# ccnor_stm32_v25-sync-unified-ss.net
KiCad netlist of a schematic drawn in EAGLE
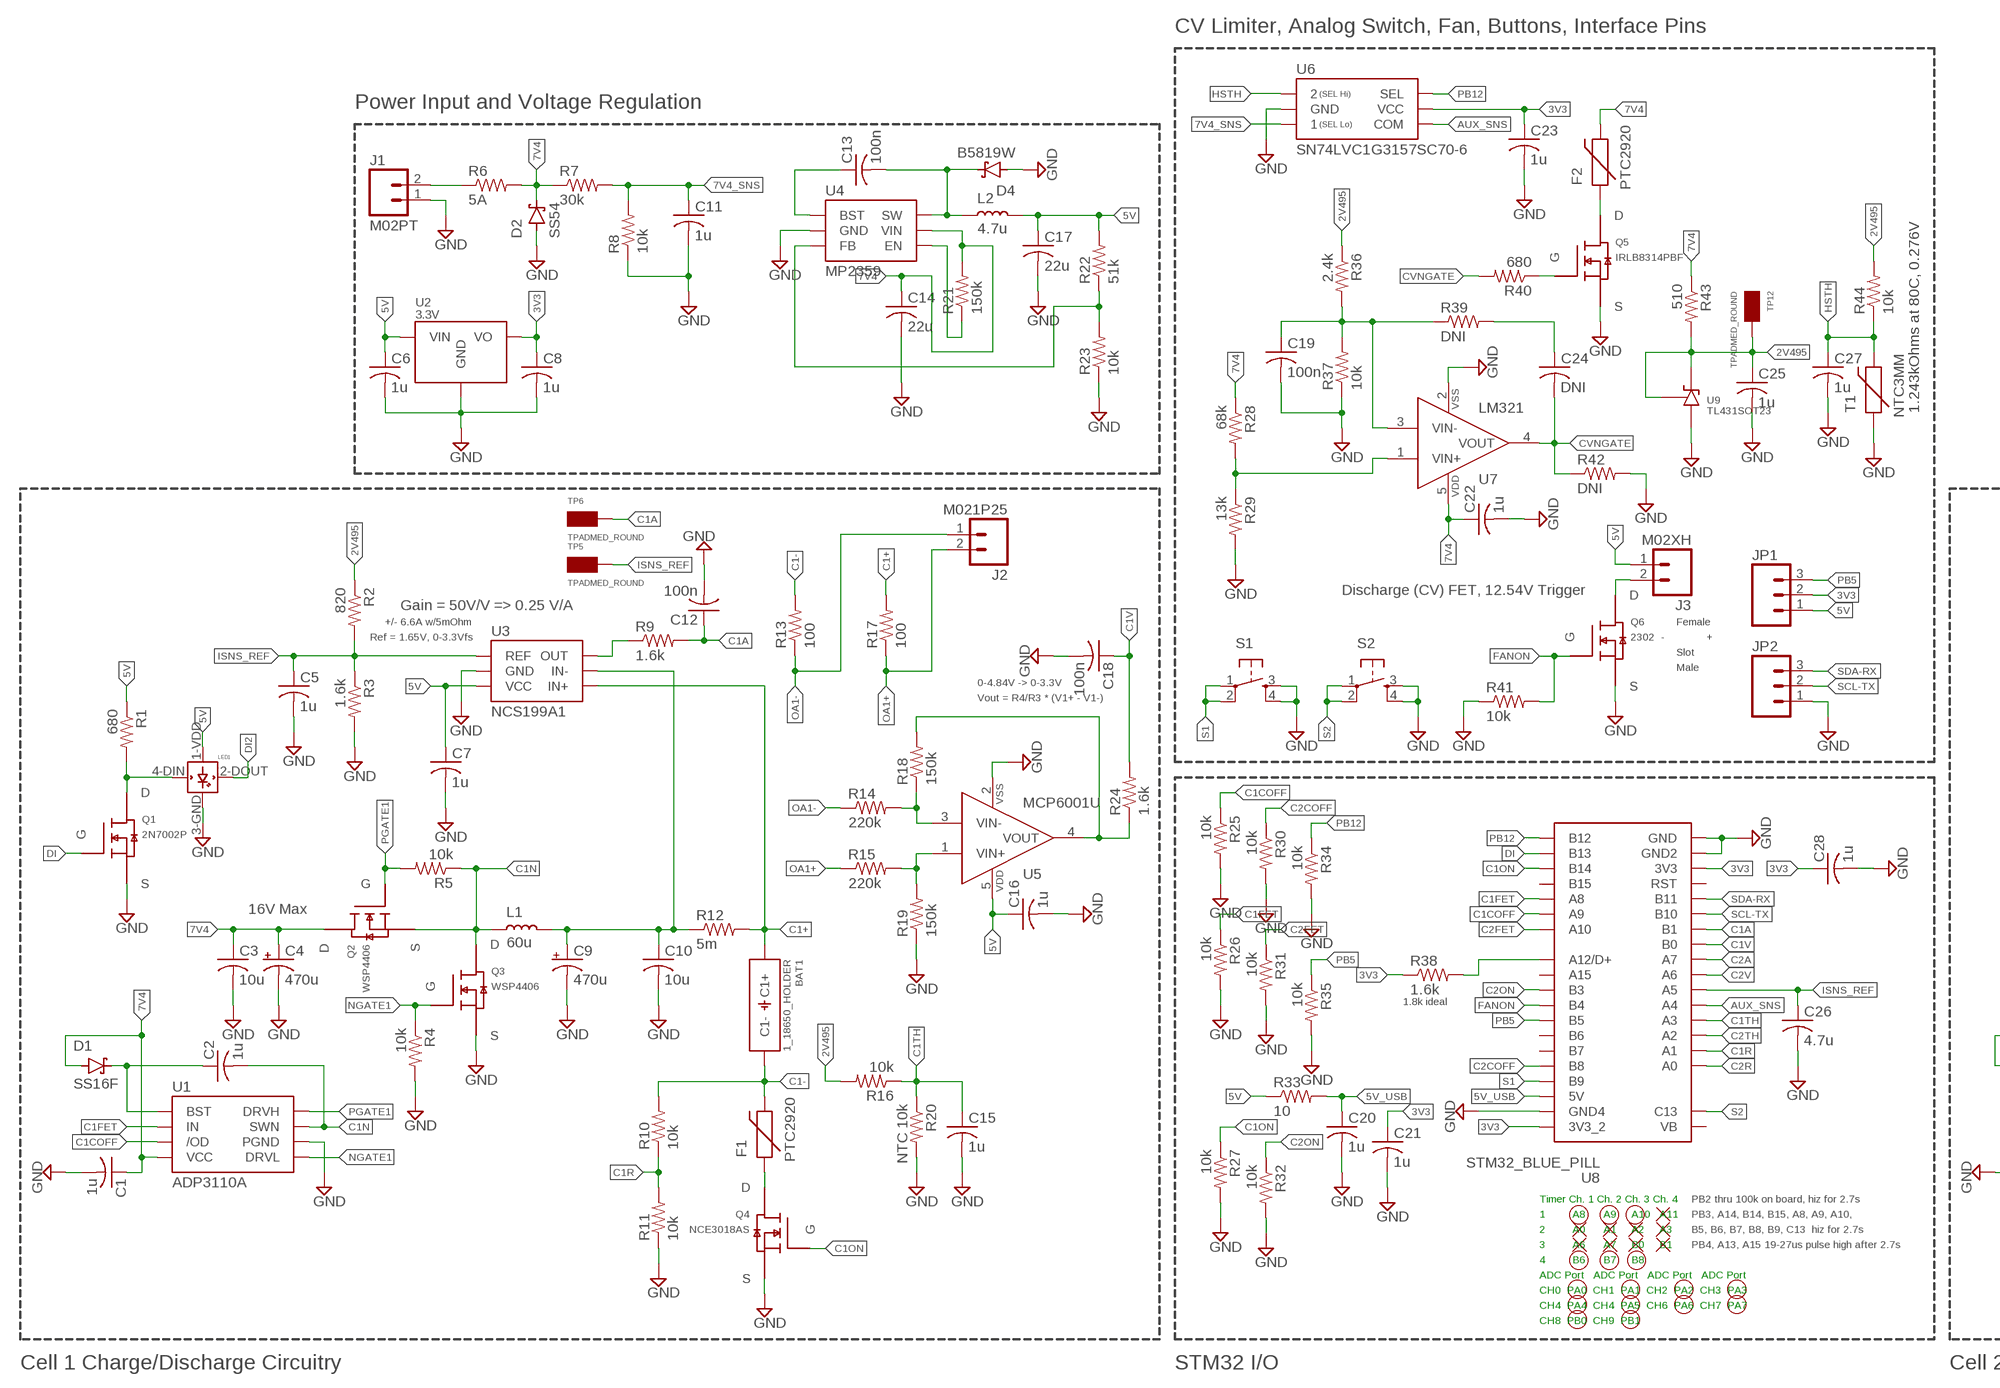
[diagram p0: schematic, sheet 1, part 1 of 2]
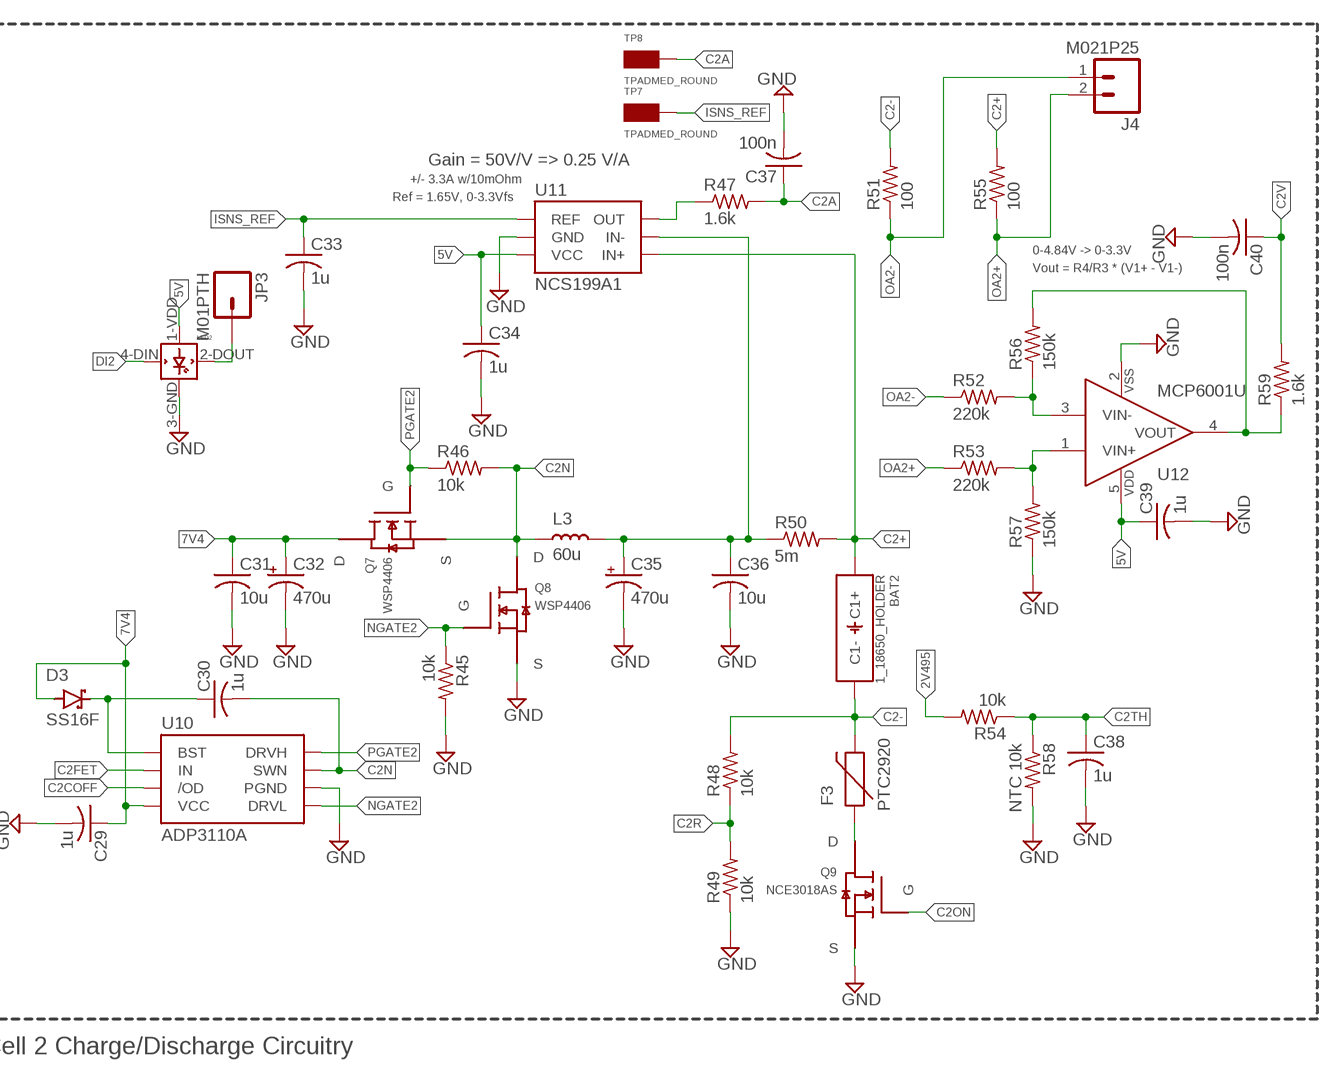
[diagram p1: schematic, sheet 1, part 2 of 2]

(export (version "E")
  (design (tool "Eeschema 10.0.6"))
  (components
    (comp (ref "BAT1")
      (value "1_18650_HOLDER")
      (footprint "eagle-import:1S_18650_SMD_NH")
      (libsource (lib "eagle-import") (part "1_18650_HOLDER"))
    )
    (comp (ref "BAT2")
      (value "1_18650_HOLDER")
      (footprint "eagle-import:1S_18650_SMD_NH")
      (libsource (lib "eagle-import") (part "1_18650_HOLDER"))
    )
    (comp (ref "C1")
      (value "1u")
      (footprint "eagle-import:C0402")
      (libsource (lib "eagle-import") (part "C-USC0402"))
    )
    (comp (ref "C2")
      (value "1u")
      (footprint "eagle-import:C0603")
      (libsource (lib "eagle-import") (part "C-USC0603"))
    )
    (comp (ref "C3")
      (value "10u")
      (footprint "eagle-import:C1206")
      (libsource (lib "eagle-import") (part "C-USC1206"))
    )
    (comp (ref "C4")
      (value "470u")
      (footprint "eagle-import:E2,5-7")
      (libsource (lib "eagle-import") (part "CPOL-USE2.5-7"))
    )
    (comp (ref "C5")
      (value "1u")
      (footprint "eagle-import:C0402")
      (libsource (lib "eagle-import") (part "C-USC0402"))
    )
    (comp (ref "C6")
      (value "1u")
      (footprint "eagle-import:C0402")
      (libsource (lib "eagle-import") (part "C-USC0402"))
    )
    (comp (ref "C7")
      (value "1u")
      (footprint "eagle-import:C0402")
      (libsource (lib "eagle-import") (part "C-USC0402"))
    )
    (comp (ref "C8")
      (value "1u")
      (footprint "eagle-import:C0402")
      (libsource (lib "eagle-import") (part "C-USC0402"))
    )
    (comp (ref "C9")
      (value "470u")
      (footprint "eagle-import:E2,5-7")
      (libsource (lib "eagle-import") (part "CPOL-USE2.5-7"))
    )
    (comp (ref "C10")
      (value "10u")
      (footprint "eagle-import:C1206")
      (libsource (lib "eagle-import") (part "C-USC1206"))
    )
    (comp (ref "C11")
      (value "1u")
      (footprint "eagle-import:C0402")
      (libsource (lib "eagle-import") (part "C-USC0402"))
    )
    (comp (ref "C12")
      (value "100n")
      (footprint "eagle-import:C0402")
      (libsource (lib "eagle-import") (part "C-USC0402"))
    )
    (comp (ref "C13")
      (value "100n")
      (footprint "eagle-import:C0402")
      (libsource (lib "eagle-import") (part "C-USC0402"))
    )
    (comp (ref "C14")
      (value "22u")
      (footprint "eagle-import:C0805")
      (libsource (lib "eagle-import") (part "C-USC0805"))
    )
    (comp (ref "C15")
      (value "1u")
      (footprint "eagle-import:C0402")
      (libsource (lib "eagle-import") (part "C-USC0402"))
    )
    (comp (ref "C16")
      (value "1u")
      (footprint "eagle-import:C0402")
      (libsource (lib "eagle-import") (part "C-USC0402"))
    )
    (comp (ref "C17")
      (value "22u")
      (footprint "eagle-import:C0603")
      (libsource (lib "eagle-import") (part "C-USC0603"))
    )
    (comp (ref "C18")
      (value "100n")
      (footprint "eagle-import:C0402")
      (libsource (lib "eagle-import") (part "C-USC0402"))
    )
    (comp (ref "C19")
      (value "100n")
      (footprint "eagle-import:C0402")
      (libsource (lib "eagle-import") (part "C-USC0402"))
    )
    (comp (ref "C20")
      (value "1u")
      (footprint "eagle-import:C0402")
      (libsource (lib "eagle-import") (part "C-USC0402"))
    )
    (comp (ref "C21")
      (value "1u")
      (footprint "eagle-import:C0402")
      (libsource (lib "eagle-import") (part "C-USC0402"))
    )
    (comp (ref "C22")
      (value "1u")
      (footprint "eagle-import:C0402")
      (libsource (lib "eagle-import") (part "C-USC0402"))
    )
    (comp (ref "C23")
      (value "1u")
      (footprint "eagle-import:C0402")
      (libsource (lib "eagle-import") (part "C-USC0402"))
    )
    (comp (ref "C24")
      (value "DNI")
      (footprint "eagle-import:C0402")
      (libsource (lib "eagle-import") (part "C-USC0402"))
    )
    (comp (ref "C25")
      (value "1u")
      (footprint "eagle-import:C0402")
      (libsource (lib "eagle-import") (part "C-USC0402"))
    )
    (comp (ref "C26")
      (value "4.7u")
      (footprint "eagle-import:C0402")
      (libsource (lib "eagle-import") (part "C-USC0402"))
    )
    (comp (ref "C27")
      (value "1u")
      (footprint "eagle-import:C0402")
      (libsource (lib "eagle-import") (part "C-USC0402"))
    )
    (comp (ref "C28")
      (value "1u")
      (footprint "eagle-import:C0402")
      (libsource (lib "eagle-import") (part "C-USC0402"))
    )
    (comp (ref "C29")
      (value "1u")
      (footprint "eagle-import:C0402")
      (libsource (lib "eagle-import") (part "C-USC0402"))
    )
    (comp (ref "C30")
      (value "1u")
      (footprint "eagle-import:C0603")
      (libsource (lib "eagle-import") (part "C-USC0603"))
    )
    (comp (ref "C31")
      (value "10u")
      (footprint "eagle-import:C1206")
      (libsource (lib "eagle-import") (part "C-USC1206"))
    )
    (comp (ref "C32")
      (value "470u")
      (footprint "eagle-import:E2,5-7")
      (libsource (lib "eagle-import") (part "CPOL-USE2.5-7"))
    )
    (comp (ref "C33")
      (value "1u")
      (footprint "eagle-import:C0402")
      (libsource (lib "eagle-import") (part "C-USC0402"))
    )
    (comp (ref "C34")
      (value "1u")
      (footprint "eagle-import:C0402")
      (libsource (lib "eagle-import") (part "C-USC0402"))
    )
    (comp (ref "C35")
      (value "470u")
      (footprint "eagle-import:E2,5-7")
      (libsource (lib "eagle-import") (part "CPOL-USE2.5-7"))
    )
    (comp (ref "C36")
      (value "10u")
      (footprint "eagle-import:C1206")
      (libsource (lib "eagle-import") (part "C-USC1206"))
    )
    (comp (ref "C37")
      (value "100n")
      (footprint "eagle-import:C0402")
      (libsource (lib "eagle-import") (part "C-USC0402"))
    )
    (comp (ref "C38")
      (value "1u")
      (footprint "eagle-import:C0402")
      (libsource (lib "eagle-import") (part "C-USC0402"))
    )
    (comp (ref "C39")
      (value "1u")
      (footprint "eagle-import:C0402")
      (libsource (lib "eagle-import") (part "C-USC0402"))
    )
    (comp (ref "C40")
      (value "100n")
      (footprint "eagle-import:C0402")
      (libsource (lib "eagle-import") (part "C-USC0402"))
    )
    (comp (ref "D1")
      (value "SS16F")
      (footprint "eagle-import:SOD123")
      (libsource (lib "eagle-import") (part "DIODE_SCHOTTKYCDBM140-G"))
    )
    (comp (ref "D2")
      (value "SS54")
      (footprint "eagle-import:SMA")
      (libsource (lib "eagle-import") (part "SS54"))
    )
    (comp (ref "D3")
      (value "SS16F")
      (footprint "eagle-import:SOD123")
      (libsource (lib "eagle-import") (part "DIODE_SCHOTTKYCDBM140-G"))
    )
    (comp (ref "D4")
      (value "B5819W")
      (footprint "eagle-import:SOD123W")
      (libsource (lib "eagle-import") (part "PMEG3020ER"))
    )
    (comp (ref "F1")
      (value "PTC2920")
      (footprint "eagle-import:2920")
      (libsource (lib "eagle-import") (part "PTC2920"))
    )
    (comp (ref "F2")
      (value "PTC2920")
      (footprint "eagle-import:2920")
      (libsource (lib "eagle-import") (part "PTC2920"))
    )
    (comp (ref "F3")
      (value "PTC2920")
      (footprint "eagle-import:2920")
      (libsource (lib "eagle-import") (part "PTC2920"))
    )
    (comp (ref "J1")
      (value "M02PT")
      (footprint "eagle-import:PHOENIXCONTACT1935161")
      (libsource (lib "eagle-import") (part "M02PT"))
    )
    (comp (ref "J2")
      (value "M021P25")
      (footprint "eagle-import:M02_1P25MM")
      (libsource (lib "eagle-import") (part "M021P25"))
    )
    (comp (ref "J3")
      (value "M02XH")
      (footprint "eagle-import:B2B-XH-A")
      (libsource (lib "eagle-import") (part "M02XH"))
    )
    (comp (ref "J4")
      (value "M021P25")
      (footprint "eagle-import:M02_1P25MM")
      (libsource (lib "eagle-import") (part "M021P25"))
    )
    (comp (ref "JP1")
      (value "M03PTH")
      (footprint "eagle-import:1X03")
      (libsource (lib "eagle-import") (part "M03PTH"))
    )
    (comp (ref "JP2")
      (value "M03PTH")
      (footprint "eagle-import:1X03")
      (libsource (lib "eagle-import") (part "M03PTH"))
    )
    (comp (ref "JP3")
      (value "M01PTH")
      (footprint "eagle-import:1X01")
      (libsource (lib "eagle-import") (part "M01PTH"))
    )
    (comp (ref "L1")
      (value "60u")
      (footprint "eagle-import:INDUCTOR_10A_8.2MMX21MM")
      (libsource (lib "eagle-import") (part "INDUCTOR10A"))
    )
    (comp (ref "L2")
      (value "4.7u")
      (footprint "eagle-import:0805")
      (libsource (lib "eagle-import") (part "INDUCTOR0805"))
    )
    (comp (ref "L3")
      (value "60u")
      (footprint "eagle-import:INDUCTOR_10A_8.2MMX21MM")
      (libsource (lib "eagle-import") (part "INDUCTOR10A"))
    )
    (comp (ref "LED1")
      (value "WS2812B")
      (footprint "eagle-import:WS2812B")
      (libsource (lib "eagle-import") (part "WS2812B"))
    )
    (comp (ref "LED2")
      (value "WS2812B")
      (footprint "eagle-import:WS2812B")
      (libsource (lib "eagle-import") (part "WS2812B"))
    )
    (comp (ref "Q1")
      (value "2N7002P")
      (footprint "eagle-import:SOT23")
      (libsource (lib "eagle-import") (part "2N7002P"))
    )
    (comp (ref "Q2")
      (value "WSP4406")
      (footprint "eagle-import:8-SOIC")
      (libsource (lib "eagle-import") (part "N-MOSFET-SOIC8"))
    )
    (comp (ref "Q3")
      (value "WSP4406")
      (footprint "eagle-import:8-SOIC")
      (libsource (lib "eagle-import") (part "N-MOSFET-SOIC8"))
    )
    (comp (ref "Q4")
      (value "NCE3018AS")
      (footprint "eagle-import:8-SOIC")
      (libsource (lib "eagle-import") (part "N-MOSFET-SOIC8"))
    )
    (comp (ref "Q5")
      (value "IRLB8314PBF")
      (footprint "eagle-import:TO-220")
      (libsource (lib "eagle-import") (part "IRLB8314PBF"))
    )
    (comp (ref "Q6")
      (value "2302")
      (footprint "eagle-import:SOT23")
      (libsource (lib "eagle-import") (part "2N7002P"))
    )
    (comp (ref "Q7")
      (value "WSP4406")
      (footprint "eagle-import:8-SOIC")
      (libsource (lib "eagle-import") (part "N-MOSFET-SOIC8"))
    )
    (comp (ref "Q8")
      (value "WSP4406")
      (footprint "eagle-import:8-SOIC")
      (libsource (lib "eagle-import") (part "N-MOSFET-SOIC8"))
    )
    (comp (ref "Q9")
      (value "NCE3018AS")
      (footprint "eagle-import:8-SOIC")
      (libsource (lib "eagle-import") (part "N-MOSFET-SOIC8"))
    )
    (comp (ref "R1")
      (value "680")
      (footprint "eagle-import:R0402")
      (libsource (lib "eagle-import") (part "R-US_R0402"))
    )
    (comp (ref "R2")
      (value "820")
      (footprint "eagle-import:R0402")
      (libsource (lib "eagle-import") (part "R-US_R0402"))
    )
    (comp (ref "R3")
      (value "1.6k")
      (footprint "eagle-import:R0402")
      (libsource (lib "eagle-import") (part "R-US_R0402"))
    )
    (comp (ref "R4")
      (value "10k")
      (footprint "eagle-import:R0402")
      (libsource (lib "eagle-import") (part "R-US_R0402"))
    )
    (comp (ref "R5")
      (value "10k")
      (footprint "eagle-import:R0402")
      (libsource (lib "eagle-import") (part "R-US_R0402"))
    )
    (comp (ref "R6")
      (value "5A")
      (footprint "eagle-import:R1206")
      (libsource (lib "eagle-import") (part "R-US_R1206"))
    )
    (comp (ref "R7")
      (value "30k")
      (footprint "eagle-import:R0402")
      (libsource (lib "eagle-import") (part "R-US_R0402"))
    )
    (comp (ref "R8")
      (value "10k")
      (footprint "eagle-import:R0402")
      (libsource (lib "eagle-import") (part "R-US_R0402"))
    )
    (comp (ref "R9")
      (value "1.6k")
      (footprint "eagle-import:R0402")
      (libsource (lib "eagle-import") (part "R-US_R0402"))
    )
    (comp (ref "R10")
      (value "10k")
      (footprint "eagle-import:R0402")
      (libsource (lib "eagle-import") (part "R-US_R0402"))
    )
    (comp (ref "R11")
      (value "10k")
      (footprint "eagle-import:R0402")
      (libsource (lib "eagle-import") (part "R-US_R0402"))
    )
    (comp (ref "R12")
      (value "5m")
      (footprint "eagle-import:R1206")
      (libsource (lib "eagle-import") (part "R-US_R1206"))
    )
    (comp (ref "R13")
      (value "100")
      (footprint "eagle-import:R0402")
      (libsource (lib "eagle-import") (part "R-US_R0402"))
    )
    (comp (ref "R14")
      (value "220k")
      (footprint "eagle-import:R0402")
      (libsource (lib "eagle-import") (part "R-US_R0402"))
    )
    (comp (ref "R15")
      (value "220k")
      (footprint "eagle-import:R0402")
      (libsource (lib "eagle-import") (part "R-US_R0402"))
    )
    (comp (ref "R16")
      (value "10k")
      (footprint "eagle-import:R0402")
      (libsource (lib "eagle-import") (part "R-US_R0402"))
    )
    (comp (ref "R17")
      (value "100")
      (footprint "eagle-import:R0402")
      (libsource (lib "eagle-import") (part "R-US_R0402"))
    )
    (comp (ref "R18")
      (value "150k")
      (footprint "eagle-import:R0402")
      (libsource (lib "eagle-import") (part "R-US_R0402"))
    )
    (comp (ref "R19")
      (value "150k")
      (footprint "eagle-import:R0402")
      (libsource (lib "eagle-import") (part "R-US_R0402"))
    )
    (comp (ref "R20")
      (value "NTC 10k")
      (footprint "eagle-import:R0402")
      (libsource (lib "eagle-import") (part "R-US_R0402"))
    )
    (comp (ref "R21")
      (value "150k")
      (footprint "eagle-import:R0402")
      (libsource (lib "eagle-import") (part "R-US_R0402"))
    )
    (comp (ref "R22")
      (value "51k")
      (footprint "eagle-import:R0402")
      (libsource (lib "eagle-import") (part "R-US_R0402"))
    )
    (comp (ref "R23")
      (value "10k")
      (footprint "eagle-import:R0402")
      (libsource (lib "eagle-import") (part "R-US_R0402"))
    )
    (comp (ref "R24")
      (value "1.6k")
      (footprint "eagle-import:R0402")
      (libsource (lib "eagle-import") (part "R-US_R0402"))
    )
    (comp (ref "R25")
      (value "10k")
      (footprint "eagle-import:R0402")
      (libsource (lib "eagle-import") (part "R-US_R0402"))
    )
    (comp (ref "R26")
      (value "10k")
      (footprint "eagle-import:R0402")
      (libsource (lib "eagle-import") (part "R-US_R0402"))
    )
    (comp (ref "R27")
      (value "10k")
      (footprint "eagle-import:R0402")
      (libsource (lib "eagle-import") (part "R-US_R0402"))
    )
    (comp (ref "R28")
      (value "68k")
      (footprint "eagle-import:R0402")
      (libsource (lib "eagle-import") (part "R-US_R0402"))
    )
    (comp (ref "R29")
      (value "13k")
      (footprint "eagle-import:R0402")
      (libsource (lib "eagle-import") (part "R-US_R0402"))
    )
    (comp (ref "R30")
      (value "10k")
      (footprint "eagle-import:R0402")
      (libsource (lib "eagle-import") (part "R-US_R0402"))
    )
    (comp (ref "R31")
      (value "10k")
      (footprint "eagle-import:R0402")
      (libsource (lib "eagle-import") (part "R-US_R0402"))
    )
    (comp (ref "R32")
      (value "10k")
      (footprint "eagle-import:R0402")
      (libsource (lib "eagle-import") (part "R-US_R0402"))
    )
    (comp (ref "R33")
      (value "10")
      (footprint "eagle-import:R0402")
      (libsource (lib "eagle-import") (part "R-US_R0402"))
    )
    (comp (ref "R34")
      (value "10k")
      (footprint "eagle-import:R0402")
      (libsource (lib "eagle-import") (part "R-US_R0402"))
    )
    (comp (ref "R35")
      (value "10k")
      (footprint "eagle-import:R0402")
      (libsource (lib "eagle-import") (part "R-US_R0402"))
    )
    (comp (ref "R36")
      (value "2.4k")
      (footprint "eagle-import:R0402")
      (libsource (lib "eagle-import") (part "R-US_R0402"))
    )
    (comp (ref "R37")
      (value "10k")
      (footprint "eagle-import:R0402")
      (libsource (lib "eagle-import") (part "R-US_R0402"))
    )
    (comp (ref "R38")
      (value "1.6k")
      (footprint "eagle-import:R0402")
      (libsource (lib "eagle-import") (part "R-US_R0402"))
    )
    (comp (ref "R39")
      (value "DNI")
      (footprint "eagle-import:R0402")
      (libsource (lib "eagle-import") (part "R-US_R0402"))
    )
    (comp (ref "R40")
      (value "680")
      (footprint "eagle-import:R0402")
      (libsource (lib "eagle-import") (part "R-US_R0402"))
    )
    (comp (ref "R41")
      (value "10k")
      (footprint "eagle-import:R0402")
      (libsource (lib "eagle-import") (part "R-US_R0402"))
    )
    (comp (ref "R42")
      (value "DNI")
      (footprint "eagle-import:R0402")
      (libsource (lib "eagle-import") (part "R-US_R0402"))
    )
    (comp (ref "R43")
      (value "510")
      (footprint "eagle-import:R0402")
      (libsource (lib "eagle-import") (part "R-US_R0402"))
    )
    (comp (ref "R44")
      (value "10k")
      (footprint "eagle-import:R0402")
      (libsource (lib "eagle-import") (part "R-US_R0402"))
    )
    (comp (ref "R45")
      (value "10k")
      (footprint "eagle-import:R0402")
      (libsource (lib "eagle-import") (part "R-US_R0402"))
    )
    (comp (ref "R46")
      (value "10k")
      (footprint "eagle-import:R0402")
      (libsource (lib "eagle-import") (part "R-US_R0402"))
    )
    (comp (ref "R47")
      (value "1.6k")
      (footprint "eagle-import:R0402")
      (libsource (lib "eagle-import") (part "R-US_R0402"))
    )
    (comp (ref "R48")
      (value "10k")
      (footprint "eagle-import:R0402")
      (libsource (lib "eagle-import") (part "R-US_R0402"))
    )
    (comp (ref "R49")
      (value "10k")
      (footprint "eagle-import:R0402")
      (libsource (lib "eagle-import") (part "R-US_R0402"))
    )
    (comp (ref "R50")
      (value "5m")
      (footprint "eagle-import:R1206")
      (libsource (lib "eagle-import") (part "R-US_R1206"))
    )
    (comp (ref "R51")
      (value "100")
      (footprint "eagle-import:R0402")
      (libsource (lib "eagle-import") (part "R-US_R0402"))
    )
    (comp (ref "R52")
      (value "220k")
      (footprint "eagle-import:R0402")
      (libsource (lib "eagle-import") (part "R-US_R0402"))
    )
    (comp (ref "R53")
      (value "220k")
      (footprint "eagle-import:R0402")
      (libsource (lib "eagle-import") (part "R-US_R0402"))
    )
    (comp (ref "R54")
      (value "10k")
      (footprint "eagle-import:R0402")
      (libsource (lib "eagle-import") (part "R-US_R0402"))
    )
    (comp (ref "R55")
      (value "100")
      (footprint "eagle-import:R0402")
      (libsource (lib "eagle-import") (part "R-US_R0402"))
    )
    (comp (ref "R56")
      (value "150k")
      (footprint "eagle-import:R0402")
      (libsource (lib "eagle-import") (part "R-US_R0402"))
    )
    (comp (ref "R57")
      (value "150k")
      (footprint "eagle-import:R0402")
      (libsource (lib "eagle-import") (part "R-US_R0402"))
    )
    (comp (ref "R58")
      (value "NTC 10k")
      (footprint "eagle-import:R0402")
      (libsource (lib "eagle-import") (part "R-US_R0402"))
    )
    (comp (ref "R59")
      (value "1.6k")
      (footprint "eagle-import:R0402")
      (libsource (lib "eagle-import") (part "R-US_R0402"))
    )
    (comp (ref "S1")
      (value "TAC_SWITCHSMD")
      (footprint "eagle-import:TACTILE_SWITCH_SMD")
      (libsource (lib "eagle-import") (part "TAC_SWITCHSMD"))
    )
    (comp (ref "S2")
      (value "TAC_SWITCHSMD")
      (footprint "eagle-import:TACTILE_SWITCH_SMD")
      (libsource (lib "eagle-import") (part "TAC_SWITCHSMD"))
    )
    (comp (ref "T1")
      (value "NTC3MM")
      (footprint "eagle-import:THERMISTOR_3MMX3MM")
      (libsource (lib "eagle-import") (part "PTCNTC3MM"))
    )
    (comp (ref "TP5")
      (value "TPADMED_ROUND")
      (footprint "eagle-import:TPAD_MED_ROUND")
      (libsource (lib "eagle-import") (part "TPADMED_ROUND"))
    )
    (comp (ref "TP6")
      (value "TPADMED_ROUND")
      (footprint "eagle-import:TPAD_MED_ROUND")
      (libsource (lib "eagle-import") (part "TPADMED_ROUND"))
    )
    (comp (ref "TP7")
      (value "TPADMED_ROUND")
      (footprint "eagle-import:TPAD_MED_ROUND")
      (libsource (lib "eagle-import") (part "TPADMED_ROUND"))
    )
    (comp (ref "TP8")
      (value "TPADMED_ROUND")
      (footprint "eagle-import:TPAD_MED_ROUND")
      (libsource (lib "eagle-import") (part "TPADMED_ROUND"))
    )
    (comp (ref "TP12")
      (value "TPADMED_ROUND")
      (footprint "eagle-import:TPAD_MED_ROUND")
      (libsource (lib "eagle-import") (part "TPADMED_ROUND"))
    )
    (comp (ref "U1")
      (value "ADP3110A")
      (footprint "eagle-import:8-SOIC")
      (libsource (lib "eagle-import") (part "ADP3110A"))
    )
    (comp (ref "U2")
      (value "3.3V")
      (footprint "eagle-import:SOT-89")
      (libsource (lib "eagle-import") (part "AP1117UR133-B"))
    )
    (comp (ref "U3")
      (value "NCS199A1")
      (footprint "eagle-import:SOT-363")
      (libsource (lib "eagle-import") (part "INA214"))
    )
    (comp (ref "U4")
      (value "MP2359")
      (footprint "eagle-import:SOT23-6")
      (libsource (lib "eagle-import") (part "JW5052C"))
    )
    (comp (ref "U5")
      (value "MCP6001U")
      (footprint "eagle-import:SOT23-5")
      (libsource (lib "eagle-import") (part "MCP6001U"))
    )
    (comp (ref "U6")
      (value "SN74LVC1G3157SC70-6")
      (footprint "eagle-import:SC70-6")
      (libsource (lib "eagle-import") (part "SN74LVC1G3157SC70-6"))
    )
    (comp (ref "U7")
      (value "LM321")
      (footprint "eagle-import:SOT23-5")
      (libsource (lib "eagle-import") (part "LM321"))
    )
    (comp (ref "U8")
      (value "STM32_BLUE_PILL")
      (footprint "eagle-import:STM32_BLUE_PILL_USABLE")
      (libsource (lib "eagle-import") (part "STM32_BLUE_PILL"))
    )
    (comp (ref "U9")
      (value "TL431SOT23")
      (footprint "eagle-import:SOT23")
      (libsource (lib "eagle-import") (part "TL431SOT23"))
    )
    (comp (ref "U10")
      (value "ADP3110A")
      (footprint "eagle-import:8-SOIC")
      (libsource (lib "eagle-import") (part "ADP3110A"))
    )
    (comp (ref "U11")
      (value "NCS199A1")
      (footprint "eagle-import:SOT-363")
      (libsource (lib "eagle-import") (part "INA214"))
    )
    (comp (ref "U12")
      (value "MCP6001U")
      (footprint "eagle-import:SOT23-5")
      (libsource (lib "eagle-import") (part "MCP6001U"))
    )
  )
  (nets
    (net (code "1") (name "2V495") (class "Default")
      (node (ref "C25") (pin "1") (pinfunction "1_1") (pintype "passive"))
      (node (ref "R16") (pin "2") (pinfunction "2_2") (pintype "passive"))
      (node (ref "R2") (pin "1") (pinfunction "1_1") (pintype "passive"))
      (node (ref "R36") (pin "1") (pinfunction "1_1") (pintype "passive"))
      (node (ref "R43") (pin "2") (pinfunction "2_2") (pintype "passive"))
      (node (ref "R44") (pin "2") (pinfunction "2_2") (pintype "passive"))
      (node (ref "R54") (pin "2") (pinfunction "2_2") (pintype "passive"))
      (node (ref "TP12") (pin "1") (pinfunction "1_1") (pintype "bidirectional"))
      (node (ref "U9") (pin "1") (pinfunction "K_1") (pintype "passive"))
      (node (ref "U9") (pin "2") (pinfunction "REF_2") (pintype "passive"))
    )
    (net (code "2") (name "3V3") (class "Default")
      (node (ref "C21") (pin "1") (pinfunction "1_1") (pintype "passive"))
      (node (ref "C23") (pin "1") (pinfunction "1_1") (pintype "passive"))
      (node (ref "C28") (pin "1") (pinfunction "1_1") (pintype "passive"))
      (node (ref "C8") (pin "1") (pinfunction "1_1") (pintype "passive"))
      (node (ref "JP1") (pin "2") (pinfunction "2_2") (pintype "passive"))
      (node (ref "R38") (pin "1") (pinfunction "1_1") (pintype "passive"))
      (node (ref "U2") (pin "1") (pinfunction "VO_1") (pintype "bidirectional"))
      (node (ref "U6") (pin "5") (pinfunction "VCC_5") (pintype "bidirectional"))
      (node (ref "U8") (pin "3V3") (pinfunction "3V3_3V3") (pintype "bidirectional"))
      (node (ref "U8") (pin "3V3_2") (pinfunction "3V3_2_3V3_2") (pintype "bidirectional"))
    )
    (net (code "3") (name "5V") (class "Default")
      (node (ref "C16") (pin "1") (pinfunction "1_1") (pintype "passive"))
      (node (ref "C17") (pin "1") (pinfunction "1_1") (pintype "passive"))
      (node (ref "C34") (pin "1") (pinfunction "1_1") (pintype "passive"))
      (node (ref "C39") (pin "1") (pinfunction "1_1") (pintype "passive"))
      (node (ref "C6") (pin "1") (pinfunction "1_1") (pintype "passive"))
      (node (ref "C7") (pin "1") (pinfunction "1_1") (pintype "passive"))
      (node (ref "J3") (pin "1") (pinfunction "1_1") (pintype "passive"))
      (node (ref "JP1") (pin "1") (pinfunction "1_1") (pintype "passive"))
      (node (ref "L2") (pin "2") (pinfunction "P$2_2") (pintype "passive"))
      (node (ref "LED1") (pin "1-VDD") (pinfunction "VDD_1-VDD") (pintype "bidirectional"))
      (node (ref "LED2") (pin "1-VDD") (pinfunction "VDD_1-VDD") (pintype "bidirectional"))
      (node (ref "R1") (pin "1") (pinfunction "1_1") (pintype "passive"))
      (node (ref "R22") (pin "2") (pinfunction "2_2") (pintype "passive"))
      (node (ref "R33") (pin "1") (pinfunction "1_1") (pintype "passive"))
      (node (ref "U11") (pin "3") (pinfunction "VCC_3") (pintype "bidirectional"))
      (node (ref "U12") (pin "5") (pinfunction "VDD_5") (pintype "bidirectional"))
      (node (ref "U2") (pin "3") (pinfunction "VIN_3") (pintype "bidirectional"))
      (node (ref "U3") (pin "3") (pinfunction "VCC_3") (pintype "bidirectional"))
      (node (ref "U5") (pin "5") (pinfunction "VDD_5") (pintype "bidirectional"))
    )
    (net (code "4") (name "5V_USB") (class "Default")
      (node (ref "C20") (pin "1") (pinfunction "1_1") (pintype "passive"))
      (node (ref "R33") (pin "2") (pinfunction "2_2") (pintype "passive"))
      (node (ref "U8") (pin "5V") (pinfunction "5V_5V") (pintype "bidirectional"))
    )
    (net (code "5") (name "7V4") (class "Default")
      (node (ref "C1") (pin "1") (pinfunction "1_1") (pintype "passive"))
      (node (ref "C14") (pin "1") (pinfunction "1_1") (pintype "passive"))
      (node (ref "C22") (pin "1") (pinfunction "1_1") (pintype "passive"))
      (node (ref "C29") (pin "1") (pinfunction "1_1") (pintype "passive"))
      (node (ref "C3") (pin "1") (pinfunction "1_1") (pintype "passive"))
      (node (ref "C31") (pin "1") (pinfunction "1_1") (pintype "passive"))
      (node (ref "C32") (pin "+") (pinfunction "+_+") (pintype "passive"))
      (node (ref "C4") (pin "+") (pinfunction "+_+") (pintype "passive"))
      (node (ref "D1") (pin "A") (pinfunction "ANODE_A") (pintype "passive"))
      (node (ref "D2") (pin "K") (pinfunction "CATHODE_K") (pintype "passive"))
      (node (ref "D3") (pin "A") (pinfunction "ANODE_A") (pintype "passive"))
      (node (ref "F2") (pin "K") (pinfunction "2_K") (pintype "bidirectional"))
      (node (ref "Q2") (pin "5") (pinfunction "D_5") (pintype "bidirectional"))
      (node (ref "Q2") (pin "6") (pinfunction "D_6") (pintype "bidirectional"))
      (node (ref "Q2") (pin "7") (pinfunction "D_7") (pintype "bidirectional"))
      (node (ref "Q2") (pin "8") (pinfunction "D_8") (pintype "bidirectional"))
      (node (ref "Q7") (pin "5") (pinfunction "D_5") (pintype "bidirectional"))
      (node (ref "Q7") (pin "6") (pinfunction "D_6") (pintype "bidirectional"))
      (node (ref "Q7") (pin "7") (pinfunction "D_7") (pintype "bidirectional"))
      (node (ref "Q7") (pin "8") (pinfunction "D_8") (pintype "bidirectional"))
      (node (ref "R21") (pin "2") (pinfunction "2_2") (pintype "passive"))
      (node (ref "R28") (pin "1") (pinfunction "1_1") (pintype "passive"))
      (node (ref "R43") (pin "1") (pinfunction "1_1") (pintype "passive"))
      (node (ref "R6") (pin "2") (pinfunction "2_2") (pintype "passive"))
      (node (ref "R7") (pin "1") (pinfunction "1_1") (pintype "passive"))
      (node (ref "U1") (pin "4") (pinfunction "VCC_4") (pintype "bidirectional"))
      (node (ref "U10") (pin "4") (pinfunction "VCC_4") (pintype "bidirectional"))
      (node (ref "U4") (pin "5") (pinfunction "VIN_5") (pintype "bidirectional"))
      (node (ref "U7") (pin "5") (pinfunction "VDD_5") (pintype "bidirectional"))
    )
    (net (code "6") (name "7V4_SNS") (class "Default")
      (node (ref "C11") (pin "1") (pinfunction "1_1") (pintype "passive"))
      (node (ref "R7") (pin "2") (pinfunction "2_2") (pintype "passive"))
      (node (ref "R8") (pin "2") (pinfunction "2_2") (pintype "passive"))
      (node (ref "U6") (pin "3") (pinfunction "1_3") (pintype "bidirectional"))
    )
    (net (code "7") (name "AUX_SNS") (class "Default")
      (node (ref "U6") (pin "4") (pinfunction "COM_4") (pintype "bidirectional"))
      (node (ref "U8") (pin "A4") (pinfunction "A4_A4") (pintype "bidirectional"))
    )
    (net (code "8") (name "C1+") (class "Default")
      (node (ref "BAT1") (pin "1+") (pinfunction "C1+_1+") (pintype "bidirectional"))
      (node (ref "R12") (pin "2") (pinfunction "2_2") (pintype "passive"))
      (node (ref "R17") (pin "2") (pinfunction "2_2") (pintype "passive"))
      (node (ref "U3") (pin "4") (pinfunction "IN+_4") (pintype "bidirectional"))
    )
    (net (code "9") (name "C1-") (class "Default")
      (node (ref "BAT1") (pin "1-") (pinfunction "C1-_1-") (pintype "bidirectional"))
      (node (ref "F1") (pin "K") (pinfunction "2_K") (pintype "bidirectional"))
      (node (ref "R10") (pin "2") (pinfunction "2_2") (pintype "passive"))
      (node (ref "R13") (pin "2") (pinfunction "2_2") (pintype "passive"))
    )
    (net (code "10") (name "C1A") (class "Default")
      (node (ref "C12") (pin "1") (pinfunction "1_1") (pintype "passive"))
      (node (ref "R9") (pin "2") (pinfunction "2_2") (pintype "passive"))
      (node (ref "TP6") (pin "1") (pinfunction "1_1") (pintype "bidirectional"))
      (node (ref "U8") (pin "B1") (pinfunction "B1_B1") (pintype "bidirectional"))
    )
    (net (code "11") (name "C1COFF") (class "Default")
      (node (ref "R25") (pin "1") (pinfunction "1_1") (pintype "passive"))
      (node (ref "U1") (pin "3") (pinfunction "/OD_3") (pintype "bidirectional"))
      (node (ref "U8") (pin "A9") (pinfunction "A9_A9") (pintype "bidirectional"))
    )
    (net (code "12") (name "C1FET") (class "Default")
      (node (ref "R26") (pin "1") (pinfunction "1_1") (pintype "passive"))
      (node (ref "U1") (pin "2") (pinfunction "IN_2") (pintype "bidirectional"))
      (node (ref "U8") (pin "A8") (pinfunction "A8_A8") (pintype "bidirectional"))
    )
    (net (code "13") (name "C1N") (class "Default")
      (node (ref "C2") (pin "2") (pinfunction "2_2") (pintype "passive"))
      (node (ref "L1") (pin "P$1") (pinfunction "P$1_P$1") (pintype "passive"))
      (node (ref "Q2") (pin "1") (pinfunction "S_1") (pintype "bidirectional"))
      (node (ref "Q2") (pin "2") (pinfunction "S_2") (pintype "bidirectional"))
      (node (ref "Q2") (pin "3") (pinfunction "S_3") (pintype "bidirectional"))
      (node (ref "Q3") (pin "5") (pinfunction "D_5") (pintype "bidirectional"))
      (node (ref "Q3") (pin "6") (pinfunction "D_6") (pintype "bidirectional"))
      (node (ref "Q3") (pin "7") (pinfunction "D_7") (pintype "bidirectional"))
      (node (ref "Q3") (pin "8") (pinfunction "D_8") (pintype "bidirectional"))
      (node (ref "R5") (pin "1") (pinfunction "1_1") (pintype "passive"))
      (node (ref "U1") (pin "7") (pinfunction "SWN_7") (pintype "bidirectional"))
    )
    (net (code "14") (name "C1ON") (class "Default")
      (node (ref "Q4") (pin "4") (pinfunction "G_4") (pintype "bidirectional"))
      (node (ref "R27") (pin "1") (pinfunction "1_1") (pintype "passive"))
      (node (ref "U8") (pin "B14") (pinfunction "B14_B14") (pintype "bidirectional"))
    )
    (net (code "15") (name "C1R") (class "Default")
      (node (ref "R10") (pin "1") (pinfunction "1_1") (pintype "passive"))
      (node (ref "R11") (pin "2") (pinfunction "2_2") (pintype "passive"))
      (node (ref "U8") (pin "A1") (pinfunction "A1_A1") (pintype "bidirectional"))
    )
    (net (code "16") (name "C1TH") (class "Default")
      (node (ref "C15") (pin "1") (pinfunction "1_1") (pintype "passive"))
      (node (ref "R16") (pin "1") (pinfunction "1_1") (pintype "passive"))
      (node (ref "R20") (pin "1") (pinfunction "1_1") (pintype "passive"))
      (node (ref "U8") (pin "A3") (pinfunction "A3_A3") (pintype "bidirectional"))
    )
    (net (code "17") (name "C1V") (class "Default")
      (node (ref "C18") (pin "1") (pinfunction "1_1") (pintype "passive"))
      (node (ref "R24") (pin "2") (pinfunction "2_2") (pintype "passive"))
      (node (ref "U8") (pin "B0") (pinfunction "B0_B0") (pintype "bidirectional"))
    )
    (net (code "18") (name "C2+") (class "Default")
      (node (ref "BAT2") (pin "1+") (pinfunction "C1+_1+") (pintype "bidirectional"))
      (node (ref "R50") (pin "2") (pinfunction "2_2") (pintype "passive"))
      (node (ref "R55") (pin "2") (pinfunction "2_2") (pintype "passive"))
      (node (ref "U11") (pin "4") (pinfunction "IN+_4") (pintype "bidirectional"))
    )
    (net (code "19") (name "C2-") (class "Default")
      (node (ref "BAT2") (pin "1-") (pinfunction "C1-_1-") (pintype "bidirectional"))
      (node (ref "F3") (pin "K") (pinfunction "2_K") (pintype "bidirectional"))
      (node (ref "R48") (pin "2") (pinfunction "2_2") (pintype "passive"))
      (node (ref "R51") (pin "2") (pinfunction "2_2") (pintype "passive"))
    )
    (net (code "20") (name "C2A") (class "Default")
      (node (ref "C37") (pin "1") (pinfunction "1_1") (pintype "passive"))
      (node (ref "R47") (pin "2") (pinfunction "2_2") (pintype "passive"))
      (node (ref "TP8") (pin "1") (pinfunction "1_1") (pintype "bidirectional"))
      (node (ref "U8") (pin "A7") (pinfunction "A7_A7") (pintype "bidirectional"))
    )
    (net (code "21") (name "C2COFF") (class "Default")
      (node (ref "R30") (pin "1") (pinfunction "1_1") (pintype "passive"))
      (node (ref "U10") (pin "3") (pinfunction "/OD_3") (pintype "bidirectional"))
      (node (ref "U8") (pin "B8") (pinfunction "B8_B8") (pintype "bidirectional"))
    )
    (net (code "22") (name "C2FET") (class "Default")
      (node (ref "R31") (pin "1") (pinfunction "1_1") (pintype "passive"))
      (node (ref "U10") (pin "2") (pinfunction "IN_2") (pintype "bidirectional"))
      (node (ref "U8") (pin "A10") (pinfunction "A10_A10") (pintype "bidirectional"))
    )
    (net (code "23") (name "C2N") (class "Default")
      (node (ref "C30") (pin "2") (pinfunction "2_2") (pintype "passive"))
      (node (ref "L3") (pin "P$1") (pinfunction "P$1_P$1") (pintype "passive"))
      (node (ref "Q7") (pin "1") (pinfunction "S_1") (pintype "bidirectional"))
      (node (ref "Q7") (pin "2") (pinfunction "S_2") (pintype "bidirectional"))
      (node (ref "Q7") (pin "3") (pinfunction "S_3") (pintype "bidirectional"))
      (node (ref "Q8") (pin "5") (pinfunction "D_5") (pintype "bidirectional"))
      (node (ref "Q8") (pin "6") (pinfunction "D_6") (pintype "bidirectional"))
      (node (ref "Q8") (pin "7") (pinfunction "D_7") (pintype "bidirectional"))
      (node (ref "Q8") (pin "8") (pinfunction "D_8") (pintype "bidirectional"))
      (node (ref "R46") (pin "2") (pinfunction "2_2") (pintype "passive"))
      (node (ref "U10") (pin "7") (pinfunction "SWN_7") (pintype "bidirectional"))
    )
    (net (code "24") (name "C2ON") (class "Default")
      (node (ref "Q9") (pin "4") (pinfunction "G_4") (pintype "bidirectional"))
      (node (ref "R32") (pin "1") (pinfunction "1_1") (pintype "passive"))
      (node (ref "U8") (pin "B3") (pinfunction "B3_B3") (pintype "bidirectional"))
    )
    (net (code "25") (name "C2R") (class "Default")
      (node (ref "R48") (pin "1") (pinfunction "1_1") (pintype "passive"))
      (node (ref "R49") (pin "2") (pinfunction "2_2") (pintype "passive"))
      (node (ref "U8") (pin "A0") (pinfunction "A0_A0") (pintype "bidirectional"))
    )
    (net (code "26") (name "C2TH") (class "Default")
      (node (ref "C38") (pin "1") (pinfunction "1_1") (pintype "passive"))
      (node (ref "R54") (pin "1") (pinfunction "1_1") (pintype "passive"))
      (node (ref "R58") (pin "1") (pinfunction "1_1") (pintype "passive"))
      (node (ref "U8") (pin "A2") (pinfunction "A2_A2") (pintype "bidirectional"))
    )
    (net (code "27") (name "C2V") (class "Default")
      (node (ref "C40") (pin "1") (pinfunction "1_1") (pintype "passive"))
      (node (ref "R59") (pin "2") (pinfunction "2_2") (pintype "passive"))
      (node (ref "U8") (pin "A6") (pinfunction "A6_A6") (pintype "bidirectional"))
    )
    (net (code "28") (name "CVNGATE") (class "Default")
      (node (ref "C24") (pin "2") (pinfunction "2_2") (pintype "passive"))
      (node (ref "R40") (pin "2") (pinfunction "2_2") (pintype "passive"))
      (node (ref "R42") (pin "1") (pinfunction "1_1") (pintype "passive"))
      (node (ref "U7") (pin "4") (pinfunction "VOUT_4") (pintype "bidirectional"))
    )
    (net (code "29") (name "DI") (class "Default")
      (node (ref "Q1") (pin "1") (pinfunction "G_1") (pintype "bidirectional"))
      (node (ref "U8") (pin "B13") (pinfunction "B13_B13") (pintype "bidirectional"))
    )
    (net (code "30") (name "DI2") (class "Default")
      (node (ref "LED1") (pin "2-DOUT") (pinfunction "DOUT_2-DOUT") (pintype "output"))
      (node (ref "LED2") (pin "4-DIN") (pinfunction "DIN_4-DIN") (pintype "input"))
    )
    (net (code "31") (name "FANON") (class "Default")
      (node (ref "Q6") (pin "1") (pinfunction "G_1") (pintype "bidirectional"))
      (node (ref "R41") (pin "2") (pinfunction "2_2") (pintype "passive"))
      (node (ref "U8") (pin "B4") (pinfunction "B4_B4") (pintype "bidirectional"))
    )
    (net (code "32") (name "GND") (class "Default")
      (node (ref "C1") (pin "2") (pinfunction "2_2") (pintype "passive"))
      (node (ref "C10") (pin "2") (pinfunction "2_2") (pintype "passive"))
      (node (ref "C11") (pin "2") (pinfunction "2_2") (pintype "passive"))
      (node (ref "C12") (pin "2") (pinfunction "2_2") (pintype "passive"))
      (node (ref "C14") (pin "2") (pinfunction "2_2") (pintype "passive"))
      (node (ref "C15") (pin "2") (pinfunction "2_2") (pintype "passive"))
      (node (ref "C16") (pin "2") (pinfunction "2_2") (pintype "passive"))
      (node (ref "C17") (pin "2") (pinfunction "2_2") (pintype "passive"))
      (node (ref "C18") (pin "2") (pinfunction "2_2") (pintype "passive"))
      (node (ref "C19") (pin "2") (pinfunction "2_2") (pintype "passive"))
      (node (ref "C20") (pin "2") (pinfunction "2_2") (pintype "passive"))
      (node (ref "C21") (pin "2") (pinfunction "2_2") (pintype "passive"))
      (node (ref "C22") (pin "2") (pinfunction "2_2") (pintype "passive"))
      (node (ref "C23") (pin "2") (pinfunction "2_2") (pintype "passive"))
      (node (ref "C25") (pin "2") (pinfunction "2_2") (pintype "passive"))
      (node (ref "C26") (pin "2") (pinfunction "2_2") (pintype "passive"))
      (node (ref "C27") (pin "2") (pinfunction "2_2") (pintype "passive"))
      (node (ref "C28") (pin "2") (pinfunction "2_2") (pintype "passive"))
      (node (ref "C29") (pin "2") (pinfunction "2_2") (pintype "passive"))
      (node (ref "C3") (pin "2") (pinfunction "2_2") (pintype "passive"))
      (node (ref "C31") (pin "2") (pinfunction "2_2") (pintype "passive"))
      (node (ref "C32") (pin "-") (pinfunction "-_-") (pintype "passive"))
      (node (ref "C33") (pin "2") (pinfunction "2_2") (pintype "passive"))
      (node (ref "C34") (pin "2") (pinfunction "2_2") (pintype "passive"))
      (node (ref "C35") (pin "-") (pinfunction "-_-") (pintype "passive"))
      (node (ref "C36") (pin "2") (pinfunction "2_2") (pintype "passive"))
      (node (ref "C37") (pin "2") (pinfunction "2_2") (pintype "passive"))
      (node (ref "C38") (pin "2") (pinfunction "2_2") (pintype "passive"))
      (node (ref "C39") (pin "2") (pinfunction "2_2") (pintype "passive"))
      (node (ref "C4") (pin "-") (pinfunction "-_-") (pintype "passive"))
      (node (ref "C40") (pin "2") (pinfunction "2_2") (pintype "passive"))
      (node (ref "C5") (pin "2") (pinfunction "2_2") (pintype "passive"))
      (node (ref "C6") (pin "2") (pinfunction "2_2") (pintype "passive"))
      (node (ref "C7") (pin "2") (pinfunction "2_2") (pintype "passive"))
      (node (ref "C8") (pin "2") (pinfunction "2_2") (pintype "passive"))
      (node (ref "C9") (pin "-") (pinfunction "-_-") (pintype "passive"))
      (node (ref "D2") (pin "A") (pinfunction "ANODE_A") (pintype "passive"))
      (node (ref "D4") (pin "A") (pinfunction "ANODE_A") (pintype "passive"))
      (node (ref "J1") (pin "1") (pinfunction "1_1") (pintype "passive"))
      (node (ref "JP2") (pin "1") (pinfunction "1_1") (pintype "passive"))
      (node (ref "LED1") (pin "3-GND") (pinfunction "GND_3-GND") (pintype "bidirectional"))
      (node (ref "LED2") (pin "3-GND") (pinfunction "GND_3-GND") (pintype "bidirectional"))
      (node (ref "Q1") (pin "2") (pinfunction "S_2") (pintype "bidirectional"))
      (node (ref "Q3") (pin "1") (pinfunction "S_1") (pintype "bidirectional"))
      (node (ref "Q3") (pin "2") (pinfunction "S_2") (pintype "bidirectional"))
      (node (ref "Q3") (pin "3") (pinfunction "S_3") (pintype "bidirectional"))
      (node (ref "Q4") (pin "1") (pinfunction "S_1") (pintype "bidirectional"))
      (node (ref "Q4") (pin "2") (pinfunction "S_2") (pintype "bidirectional"))
      (node (ref "Q4") (pin "3") (pinfunction "S_3") (pintype "bidirectional"))
      (node (ref "Q5") (pin "3") (pinfunction "S_3") (pintype "bidirectional"))
      (node (ref "Q6") (pin "2") (pinfunction "S_2") (pintype "bidirectional"))
      (node (ref "Q8") (pin "1") (pinfunction "S_1") (pintype "bidirectional"))
      (node (ref "Q8") (pin "2") (pinfunction "S_2") (pintype "bidirectional"))
      (node (ref "Q8") (pin "3") (pinfunction "S_3") (pintype "bidirectional"))
      (node (ref "Q9") (pin "1") (pinfunction "S_1") (pintype "bidirectional"))
      (node (ref "Q9") (pin "2") (pinfunction "S_2") (pintype "bidirectional"))
      (node (ref "Q9") (pin "3") (pinfunction "S_3") (pintype "bidirectional"))
      (node (ref "R11") (pin "1") (pinfunction "1_1") (pintype "passive"))
      (node (ref "R19") (pin "1") (pinfunction "1_1") (pintype "passive"))
      (node (ref "R20") (pin "2") (pinfunction "2_2") (pintype "passive"))
      (node (ref "R23") (pin "1") (pinfunction "1_1") (pintype "passive"))
      (node (ref "R25") (pin "2") (pinfunction "2_2") (pintype "passive"))
      (node (ref "R26") (pin "2") (pinfunction "2_2") (pintype "passive"))
      (node (ref "R27") (pin "2") (pinfunction "2_2") (pintype "passive"))
      (node (ref "R29") (pin "2") (pinfunction "2_2") (pintype "passive"))
      (node (ref "R3") (pin "2") (pinfunction "2_2") (pintype "passive"))
      (node (ref "R30") (pin "2") (pinfunction "2_2") (pintype "passive"))
      (node (ref "R31") (pin "2") (pinfunction "2_2") (pintype "passive"))
      (node (ref "R32") (pin "2") (pinfunction "2_2") (pintype "passive"))
      (node (ref "R34") (pin "2") (pinfunction "2_2") (pintype "passive"))
      (node (ref "R35") (pin "2") (pinfunction "2_2") (pintype "passive"))
      (node (ref "R37") (pin "1") (pinfunction "1_1") (pintype "passive"))
      (node (ref "R4") (pin "2") (pinfunction "2_2") (pintype "passive"))
      (node (ref "R41") (pin "1") (pinfunction "1_1") (pintype "passive"))
      (node (ref "R42") (pin "2") (pinfunction "2_2") (pintype "passive"))
      (node (ref "R45") (pin "2") (pinfunction "2_2") (pintype "passive"))
      (node (ref "R49") (pin "1") (pinfunction "1_1") (pintype "passive"))
      (node (ref "R57") (pin "1") (pinfunction "1_1") (pintype "passive"))
      (node (ref "R58") (pin "2") (pinfunction "2_2") (pintype "passive"))
      (node (ref "R8") (pin "1") (pinfunction "1_1") (pintype "passive"))
      (node (ref "S1") (pin "3") (pinfunction "3_3") (pintype "passive"))
      (node (ref "S1") (pin "4") (pinfunction "4_4") (pintype "passive"))
      (node (ref "S2") (pin "3") (pinfunction "3_3") (pintype "passive"))
      (node (ref "S2") (pin "4") (pinfunction "4_4") (pintype "passive"))
      (node (ref "T1") (pin "1") (pinfunction "1_1") (pintype "bidirectional"))
      (node (ref "U1") (pin "6") (pinfunction "PGND_6") (pintype "bidirectional"))
      (node (ref "U10") (pin "6") (pinfunction "PGND_6") (pintype "bidirectional"))
      (node (ref "U11") (pin "2") (pinfunction "GND_2") (pintype "bidirectional"))
      (node (ref "U12") (pin "2") (pinfunction "VSS_2") (pintype "bidirectional"))
      (node (ref "U2") (pin "2") (pinfunction "GND_2") (pintype "bidirectional"))
      (node (ref "U2") (pin "2@1") (pinfunction "GND_2@1") (pintype "bidirectional"))
      (node (ref "U3") (pin "2") (pinfunction "GND_2") (pintype "bidirectional"))
      (node (ref "U4") (pin "2") (pinfunction "GND_2") (pintype "bidirectional"))
      (node (ref "U5") (pin "2") (pinfunction "VSS_2") (pintype "bidirectional"))
      (node (ref "U6") (pin "2") (pinfunction "GND_2") (pintype "bidirectional"))
      (node (ref "U7") (pin "2") (pinfunction "VSS_2") (pintype "bidirectional"))
      (node (ref "U8") (pin "GND") (pinfunction "GND_GND") (pintype "bidirectional"))
      (node (ref "U8") (pin "GND2") (pinfunction "GND2_GND2") (pintype "bidirectional"))
      (node (ref "U8") (pin "GND4") (pinfunction "GND4_GND4") (pintype "bidirectional"))
      (node (ref "U9") (pin "3") (pinfunction "A_3") (pintype "passive"))
    )
    (net (code "33") (name "HSTH") (class "Default")
      (node (ref "C27") (pin "1") (pinfunction "1_1") (pintype "passive"))
      (node (ref "R44") (pin "1") (pinfunction "1_1") (pintype "passive"))
      (node (ref "T1") (pin "2") (pinfunction "2_2") (pintype "bidirectional"))
      (node (ref "U6") (pin "1") (pinfunction "2_1") (pintype "bidirectional"))
    )
    (net (code "34") (name "ISNS_REF") (class "Default")
      (node (ref "C26") (pin "1") (pinfunction "1_1") (pintype "passive"))
      (node (ref "C33") (pin "1") (pinfunction "1_1") (pintype "passive"))
      (node (ref "C5") (pin "1") (pinfunction "1_1") (pintype "passive"))
      (node (ref "R2") (pin "2") (pinfunction "2_2") (pintype "passive"))
      (node (ref "R3") (pin "1") (pinfunction "1_1") (pintype "passive"))
      (node (ref "TP5") (pin "1") (pinfunction "1_1") (pintype "bidirectional"))
      (node (ref "TP7") (pin "1") (pinfunction "1_1") (pintype "bidirectional"))
      (node (ref "U11") (pin "1") (pinfunction "REF_1") (pintype "bidirectional"))
      (node (ref "U3") (pin "1") (pinfunction "REF_1") (pintype "bidirectional"))
      (node (ref "U8") (pin "A5") (pinfunction "A5_A5") (pintype "bidirectional"))
    )
    (net (code "35") (name "NGATE1") (class "Default")
      (node (ref "Q3") (pin "4") (pinfunction "G_4") (pintype "bidirectional"))
      (node (ref "R4") (pin "1") (pinfunction "1_1") (pintype "passive"))
      (node (ref "U1") (pin "5") (pinfunction "DRVL_5") (pintype "bidirectional"))
    )
    (net (code "36") (name "NGATE2") (class "Default")
      (node (ref "Q8") (pin "4") (pinfunction "G_4") (pintype "bidirectional"))
      (node (ref "R45") (pin "1") (pinfunction "1_1") (pintype "passive"))
      (node (ref "U10") (pin "5") (pinfunction "DRVL_5") (pintype "bidirectional"))
    )
    (net (code "37") (name "Net-(C24-Pad1)") (class "Default")
      (node (ref "C24") (pin "1") (pinfunction "1_1") (pintype "passive"))
      (node (ref "R39") (pin "2") (pinfunction "2_2") (pintype "passive"))
    )
    (net (code "38") (name "Net-(D1-CATHODE)") (class "Default")
      (node (ref "C2") (pin "1") (pinfunction "1_1") (pintype "passive"))
      (node (ref "D1") (pin "K") (pinfunction "CATHODE_K") (pintype "passive"))
      (node (ref "U1") (pin "1") (pinfunction "BST_1") (pintype "bidirectional"))
    )
    (net (code "39") (name "Net-(D3-CATHODE)") (class "Default")
      (node (ref "C30") (pin "1") (pinfunction "1_1") (pintype "passive"))
      (node (ref "D3") (pin "K") (pinfunction "CATHODE_K") (pintype "passive"))
      (node (ref "U10") (pin "1") (pinfunction "BST_1") (pintype "bidirectional"))
    )
    (net (code "40") (name "Net-(D4-CATHODE)") (class "Default")
      (node (ref "C13") (pin "2") (pinfunction "2_2") (pintype "passive"))
      (node (ref "D4") (pin "K") (pinfunction "CATHODE_K") (pintype "passive"))
      (node (ref "L2") (pin "1") (pinfunction "P$1_1") (pintype "passive"))
      (node (ref "U4") (pin "6") (pinfunction "SW_6") (pintype "bidirectional"))
    )
    (net (code "41") (name "Net-(F1-1)") (class "Default")
      (node (ref "F1") (pin "A") (pinfunction "1_A") (pintype "bidirectional"))
      (node (ref "Q4") (pin "5") (pinfunction "D_5") (pintype "bidirectional"))
      (node (ref "Q4") (pin "6") (pinfunction "D_6") (pintype "bidirectional"))
      (node (ref "Q4") (pin "7") (pinfunction "D_7") (pintype "bidirectional"))
      (node (ref "Q4") (pin "8") (pinfunction "D_8") (pintype "bidirectional"))
    )
    (net (code "42") (name "Net-(F2-1)") (class "Default")
      (node (ref "F2") (pin "A") (pinfunction "1_A") (pintype "bidirectional"))
      (node (ref "Q5") (pin "2") (pinfunction "D_2") (pintype "bidirectional"))
    )
    (net (code "43") (name "Net-(F3-1)") (class "Default")
      (node (ref "F3") (pin "A") (pinfunction "1_A") (pintype "bidirectional"))
      (node (ref "Q9") (pin "5") (pinfunction "D_5") (pintype "bidirectional"))
      (node (ref "Q9") (pin "6") (pinfunction "D_6") (pintype "bidirectional"))
      (node (ref "Q9") (pin "7") (pinfunction "D_7") (pintype "bidirectional"))
      (node (ref "Q9") (pin "8") (pinfunction "D_8") (pintype "bidirectional"))
    )
    (net (code "44") (name "Net-(J1-Pad2)") (class "Default")
      (node (ref "J1") (pin "2") (pinfunction "2_2") (pintype "passive"))
      (node (ref "R6") (pin "1") (pinfunction "1_1") (pintype "passive"))
    )
    (net (code "45") (name "Net-(LED1-DIN)") (class "Default")
      (node (ref "LED1") (pin "4-DIN") (pinfunction "DIN_4-DIN") (pintype "input"))
      (node (ref "Q1") (pin "3") (pinfunction "D_3") (pintype "bidirectional"))
      (node (ref "R1") (pin "2") (pinfunction "2_2") (pintype "passive"))
    )
    (net (code "46") (name "Net-(LED2-DOUT)") (class "Default")
      (node (ref "JP3") (pin "1") (pinfunction "1_1") (pintype "passive"))
      (node (ref "LED2") (pin "2-DOUT") (pinfunction "DOUT_2-DOUT") (pintype "output"))
    )
    (net (code "47") (name "Net-(Q5-G)") (class "Default")
      (node (ref "Q5") (pin "1") (pinfunction "G_1") (pintype "bidirectional"))
      (node (ref "R40") (pin "1") (pinfunction "1_1") (pintype "passive"))
    )
    (net (code "48") (name "Net-(Q6-D)") (class "Default")
      (node (ref "J3") (pin "2") (pinfunction "2_2") (pintype "passive"))
      (node (ref "Q6") (pin "3") (pinfunction "D_3") (pintype "bidirectional"))
    )
    (net (code "49") (name "Net-(U3-IN-)") (class "Default")
      (node (ref "C10") (pin "1") (pinfunction "1_1") (pintype "passive"))
      (node (ref "C9") (pin "+") (pinfunction "+_+") (pintype "passive"))
      (node (ref "L1") (pin "P$2") (pinfunction "P$2_P$2") (pintype "passive"))
      (node (ref "R12") (pin "1") (pinfunction "1_1") (pintype "passive"))
      (node (ref "U3") (pin "5") (pinfunction "IN-_5") (pintype "bidirectional"))
    )
    (net (code "50") (name "Net-(U3-OUT)") (class "Default")
      (node (ref "R9") (pin "1") (pinfunction "1_1") (pintype "passive"))
      (node (ref "U3") (pin "6") (pinfunction "OUT_6") (pintype "bidirectional"))
    )
    (net (code "51") (name "Net-(U4-BST)") (class "Default")
      (node (ref "C13") (pin "1") (pinfunction "1_1") (pintype "passive"))
      (node (ref "U4") (pin "1") (pinfunction "BST_1") (pintype "bidirectional"))
    )
    (net (code "52") (name "Net-(U4-EN)") (class "Default")
      (node (ref "R21") (pin "1") (pinfunction "1_1") (pintype "passive"))
      (node (ref "U4") (pin "4") (pinfunction "EN_4") (pintype "bidirectional"))
    )
    (net (code "53") (name "Net-(U4-FB)") (class "Default")
      (node (ref "R22") (pin "1") (pinfunction "1_1") (pintype "passive"))
      (node (ref "R23") (pin "2") (pinfunction "2_2") (pintype "passive"))
      (node (ref "U4") (pin "3") (pinfunction "FB_3") (pintype "bidirectional"))
    )
    (net (code "54") (name "Net-(U5-VIN+)") (class "Default")
      (node (ref "R15") (pin "2") (pinfunction "2_2") (pintype "passive"))
      (node (ref "R19") (pin "2") (pinfunction "2_2") (pintype "passive"))
      (node (ref "U5") (pin "1") (pinfunction "VIN+_1") (pintype "bidirectional"))
    )
    (net (code "55") (name "Net-(U5-VIN-)") (class "Default")
      (node (ref "R14") (pin "2") (pinfunction "2_2") (pintype "passive"))
      (node (ref "R18") (pin "1") (pinfunction "1_1") (pintype "passive"))
      (node (ref "U5") (pin "3") (pinfunction "VIN-_3") (pintype "bidirectional"))
    )
    (net (code "56") (name "Net-(U5-VOUT)") (class "Default")
      (node (ref "R18") (pin "2") (pinfunction "2_2") (pintype "passive"))
      (node (ref "R24") (pin "1") (pinfunction "1_1") (pintype "passive"))
      (node (ref "U5") (pin "4") (pinfunction "VOUT_4") (pintype "bidirectional"))
    )
    (net (code "57") (name "Net-(U7-VIN+)") (class "Default")
      (node (ref "R28") (pin "2") (pinfunction "2_2") (pintype "passive"))
      (node (ref "R29") (pin "1") (pinfunction "1_1") (pintype "passive"))
      (node (ref "U7") (pin "1") (pinfunction "VIN+_1") (pintype "bidirectional"))
    )
    (net (code "58") (name "Net-(U7-VIN-)") (class "Default")
      (node (ref "C19") (pin "1") (pinfunction "1_1") (pintype "passive"))
      (node (ref "R36") (pin "2") (pinfunction "2_2") (pintype "passive"))
      (node (ref "R37") (pin "2") (pinfunction "2_2") (pintype "passive"))
      (node (ref "R39") (pin "1") (pinfunction "1_1") (pintype "passive"))
      (node (ref "U7") (pin "3") (pinfunction "VIN-_3") (pintype "bidirectional"))
    )
    (net (code "59") (name "Net-(U8-A12{slash}D+)") (class "Default")
      (node (ref "R38") (pin "2") (pinfunction "2_2") (pintype "passive"))
      (node (ref "U8") (pin "A12") (pinfunction "A12/D+_A12") (pintype "bidirectional"))
    )
    (net (code "60") (name "Net-(U11-IN-)") (class "Default")
      (node (ref "C35") (pin "+") (pinfunction "+_+") (pintype "passive"))
      (node (ref "C36") (pin "1") (pinfunction "1_1") (pintype "passive"))
      (node (ref "L3") (pin "P$2") (pinfunction "P$2_P$2") (pintype "passive"))
      (node (ref "R50") (pin "1") (pinfunction "1_1") (pintype "passive"))
      (node (ref "U11") (pin "5") (pinfunction "IN-_5") (pintype "bidirectional"))
    )
    (net (code "61") (name "Net-(U11-OUT)") (class "Default")
      (node (ref "R47") (pin "1") (pinfunction "1_1") (pintype "passive"))
      (node (ref "U11") (pin "6") (pinfunction "OUT_6") (pintype "bidirectional"))
    )
    (net (code "62") (name "Net-(U12-VIN+)") (class "Default")
      (node (ref "R53") (pin "2") (pinfunction "2_2") (pintype "passive"))
      (node (ref "R57") (pin "2") (pinfunction "2_2") (pintype "passive"))
      (node (ref "U12") (pin "1") (pinfunction "VIN+_1") (pintype "bidirectional"))
    )
    (net (code "63") (name "Net-(U12-VIN-)") (class "Default")
      (node (ref "R52") (pin "2") (pinfunction "2_2") (pintype "passive"))
      (node (ref "R56") (pin "1") (pinfunction "1_1") (pintype "passive"))
      (node (ref "U12") (pin "3") (pinfunction "VIN-_3") (pintype "bidirectional"))
    )
    (net (code "64") (name "Net-(U12-VOUT)") (class "Default")
      (node (ref "R56") (pin "2") (pinfunction "2_2") (pintype "passive"))
      (node (ref "R59") (pin "1") (pinfunction "1_1") (pintype "passive"))
      (node (ref "U12") (pin "4") (pinfunction "VOUT_4") (pintype "bidirectional"))
    )
    (net (code "65") (name "OA1+") (class "Default")
      (node (ref "J2") (pin "2") (pinfunction "2_2") (pintype "passive"))
      (node (ref "R15") (pin "1") (pinfunction "1_1") (pintype "passive"))
      (node (ref "R17") (pin "1") (pinfunction "1_1") (pintype "passive"))
    )
    (net (code "66") (name "OA1-") (class "Default")
      (node (ref "J2") (pin "1") (pinfunction "1_1") (pintype "passive"))
      (node (ref "R13") (pin "1") (pinfunction "1_1") (pintype "passive"))
      (node (ref "R14") (pin "1") (pinfunction "1_1") (pintype "passive"))
    )
    (net (code "67") (name "OA2+") (class "Default")
      (node (ref "J4") (pin "2") (pinfunction "2_2") (pintype "passive"))
      (node (ref "R53") (pin "1") (pinfunction "1_1") (pintype "passive"))
      (node (ref "R55") (pin "1") (pinfunction "1_1") (pintype "passive"))
    )
    (net (code "68") (name "OA2-") (class "Default")
      (node (ref "J4") (pin "1") (pinfunction "1_1") (pintype "passive"))
      (node (ref "R51") (pin "1") (pinfunction "1_1") (pintype "passive"))
      (node (ref "R52") (pin "1") (pinfunction "1_1") (pintype "passive"))
    )
    (net (code "69") (name "PB5") (class "Default")
      (node (ref "JP1") (pin "3") (pinfunction "3_3") (pintype "passive"))
      (node (ref "R35") (pin "1") (pinfunction "1_1") (pintype "passive"))
      (node (ref "U8") (pin "B5") (pinfunction "B5_B5") (pintype "bidirectional"))
    )
    (net (code "70") (name "PB12") (class "Default")
      (node (ref "R34") (pin "1") (pinfunction "1_1") (pintype "passive"))
      (node (ref "U6") (pin "6") (pinfunction "SEL_6") (pintype "bidirectional"))
      (node (ref "U8") (pin "B12") (pinfunction "B12_B12") (pintype "bidirectional"))
    )
    (net (code "71") (name "PGATE1") (class "Default")
      (node (ref "Q2") (pin "4") (pinfunction "G_4") (pintype "bidirectional"))
      (node (ref "R5") (pin "2") (pinfunction "2_2") (pintype "passive"))
      (node (ref "U1") (pin "8") (pinfunction "DRVH_8") (pintype "bidirectional"))
    )
    (net (code "72") (name "PGATE2") (class "Default")
      (node (ref "Q7") (pin "4") (pinfunction "G_4") (pintype "bidirectional"))
      (node (ref "R46") (pin "1") (pinfunction "1_1") (pintype "passive"))
      (node (ref "U10") (pin "8") (pinfunction "DRVH_8") (pintype "bidirectional"))
    )
    (net (code "73") (name "S1") (class "Default")
      (node (ref "S1") (pin "1") (pinfunction "1_1") (pintype "passive"))
      (node (ref "S1") (pin "2") (pinfunction "2_2") (pintype "passive"))
      (node (ref "U8") (pin "B9") (pinfunction "B9_B9") (pintype "bidirectional"))
    )
    (net (code "74") (name "S2") (class "Default")
      (node (ref "S2") (pin "1") (pinfunction "1_1") (pintype "passive"))
      (node (ref "S2") (pin "2") (pinfunction "2_2") (pintype "passive"))
      (node (ref "U8") (pin "C13") (pinfunction "C13_C13") (pintype "bidirectional"))
    )
    (net (code "75") (name "SCL-TX") (class "Default")
      (node (ref "JP2") (pin "2") (pinfunction "2_2") (pintype "passive"))
      (node (ref "U8") (pin "B10") (pinfunction "B10_B10") (pintype "bidirectional"))
    )
    (net (code "76") (name "SDA-RX") (class "Default")
      (node (ref "JP2") (pin "3") (pinfunction "3_3") (pintype "passive"))
      (node (ref "U8") (pin "B11") (pinfunction "B11_B11") (pintype "bidirectional"))
    )
    (net (code "77") (name "unconnected-(U8-PadA15)") (class "Default")
      (node (ref "U8") (pin "A15") (pinfunction "A15_A15") (pintype "bidirectional"))
    )
    (net (code "78") (name "unconnected-(U8-PadB6)") (class "Default")
      (node (ref "U8") (pin "B6") (pinfunction "B6_B6") (pintype "bidirectional"))
    )
    (net (code "79") (name "unconnected-(U8-PadB7)") (class "Default")
      (node (ref "U8") (pin "B7") (pinfunction "B7_B7") (pintype "bidirectional"))
    )
    (net (code "80") (name "unconnected-(U8-PadB15)") (class "Default")
      (node (ref "U8") (pin "B15") (pinfunction "B15_B15") (pintype "bidirectional"))
    )
    (net (code "81") (name "unconnected-(U8-PadRST)") (class "Default")
      (node (ref "U8") (pin "RST") (pinfunction "RST_RST") (pintype "bidirectional"))
    )
    (net (code "82") (name "unconnected-(U8-VB-PadVBAT)") (class "Default")
      (node (ref "U8") (pin "VBAT") (pinfunction "VB_VBAT") (pintype "bidirectional"))
    )
  )
)
